# MD1800_5V800mA.net
KiCad netlist of a schematic drawn in Altium Designer
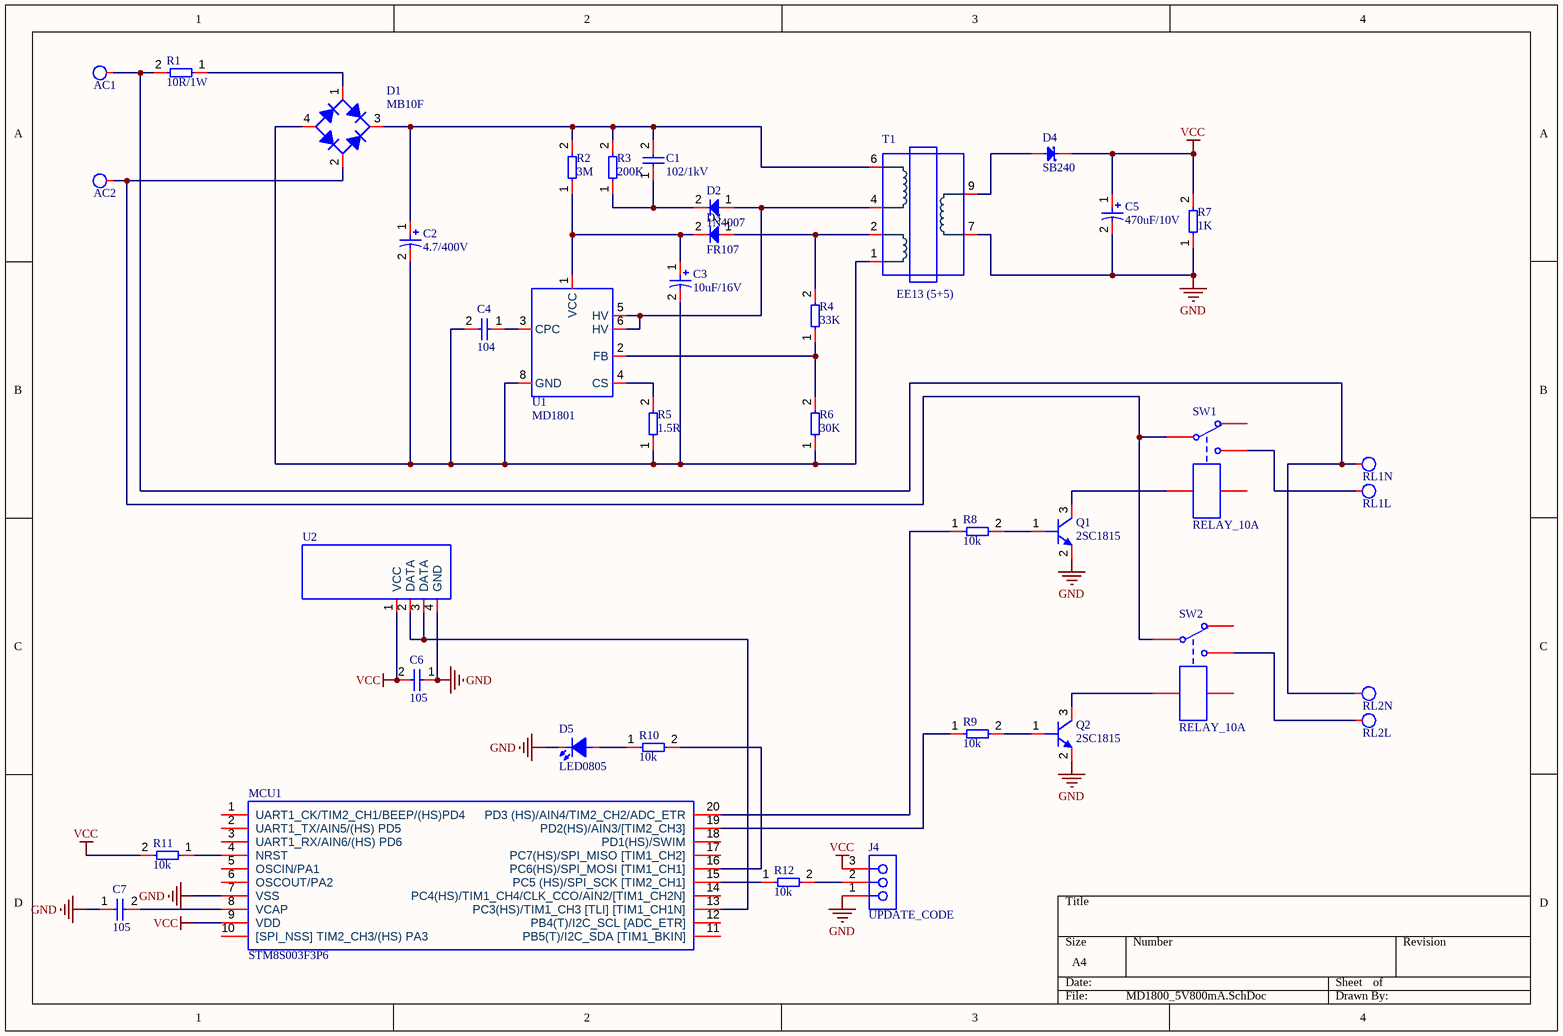
[diagram p0: MD1800_5V800mA.SchDoc]

(export (version "E")
  (design (tool "Eeschema 10.0.6"))
  (components
    (comp (ref "AC1")
      (value "AC")
      (footprint "SolderPoint")
      (libsource (lib "Lib31082020") (part "SolderPoint"))
    )
    (comp (ref "AC2")
      (value "AC")
      (footprint "SolderPoint")
      (libsource (lib "Lib31082020") (part "SolderPoint"))
    )
    (comp (ref "C1") (value "102/1kV") (footprint "C0805") (libsource (lib "Lib31082020") (part "C0805")))
    (comp (ref "C2")
      (value "4.7/400V")
      (footprint "CAP_RAD_3.5mm")
      (libsource (lib "Lib31082020") (part "Capacitor(Radian)"))
    )
    (comp (ref "C3")
      (value "10uF/16V")
      (footprint "CAP_RAD_2.5mm")
      (libsource (lib "Lib31082020") (part "Capacitor(Radian)"))
    )
    (comp (ref "C4") (value "104") (footprint "C0805") (libsource (lib "Lib31082020") (part "C0805")))
    (comp (ref "C5")
      (value "470uF/10V")
      (footprint "CAP_RAD_3.5mm")
      (libsource (lib "Lib31082020") (part "Capacitor(Radian)"))
    )
    (comp (ref "C6") (value "105") (footprint "C0805") (libsource (lib "Lib31082020") (part "C0805")))
    (comp (ref "C7") (value "105") (footprint "C0805") (libsource (lib "Lib31082020") (part "C0805")))
    (comp (ref "D1")
      (value "MB10F")
      (footprint "MB10F-TMBS")
      (description "1A 1000V")
      (libsource (lib "Lib31082020") (part "MB10F"))
    )
    (comp (ref "D2")
      (value "1N4007")
      (footprint "SOD-123FL")
      (description "1A 1000V")
      (libsource (lib "Lib31082020") (part "Diode FR107"))
    )
    (comp (ref "D3")
      (value "FR107")
      (footprint "SOD-123FL")
      (description "1A 1000V")
      (libsource (lib "Lib31082020") (part "Diode FR107"))
    )
    (comp (ref "D4")
      (value "SB240")
      (footprint "DO-214AC(SMA)")
      (libsource (lib "Lib31082020") (part "Diode Schottky"))
    )
    (comp (ref "D5")
      (value "LED0805")
      (footprint "L0805RED")
      (libsource (lib "Lib31082020") (part "LED0805"))
    )
    (comp (ref "J4")
      (value "UPDATE_CODE")
      (footprint "Header 3x1 TH Pitch 2.54mm")
      (libsource (lib "Lib31082020") (part "Header 3x1 TH Pitch 2.54mm"))
    )
    (comp (ref "MCU1")
      (value "STM8S003F3P6")
      (footprint "TSSOP20_0.65_4.4")
      (libsource (lib "Lib31082020") (part "STM8S003F3P6"))
    )
    (comp (ref "Q1")
      (value "2SC1815")
      (footprint "SOT23-3")
      (libsource (lib "Lib31082020") (part "2SC1815 (SOT-23)"))
    )
    (comp (ref "Q2")
      (value "2SC1815")
      (footprint "SOT23-3")
      (libsource (lib "Lib31082020") (part "2SC1815 (SOT-23)"))
    )
    (comp (ref "R1")
      (value "10R/1W")
      (footprint "RES-1W-V-MF")
      (libsource (lib "Lib31082020") (part "Resistors THD"))
    )
    (comp (ref "R2") (value "3M") (footprint "R0805") (libsource (lib "") (part "Resistor SMD_1")))
    (comp (ref "R3") (value "200K") (footprint "R0805") (libsource (lib "") (part "Resistor SMD_1")))
    (comp (ref "R4") (value "33K") (footprint "R0805") (libsource (lib "") (part "Resistor SMD_1")))
    (comp (ref "R5") (value "1.5R") (footprint "R0805") (libsource (lib "") (part "Resistor SMD_1")))
    (comp (ref "R6") (value "30K") (footprint "R0805") (libsource (lib "") (part "Resistor SMD_1")))
    (comp (ref "R7") (value "1K") (footprint "R0805") (libsource (lib "") (part "Resistor SMD_1")))
    (comp (ref "R8") (value "10k") (footprint "R0805") (libsource (lib "Lib31082020") (part "Resistor SMD")))
    (comp (ref "R9") (value "10k") (footprint "R0805") (libsource (lib "Lib31082020") (part "Resistor SMD")))
    (comp (ref "R10") (value "10k") (footprint "R0805") (libsource (lib "Lib31082020") (part "Resistor SMD")))
    (comp (ref "R11") (value "10k") (footprint "R0805") (libsource (lib "") (part "Resistor SMD_2")))
    (comp (ref "R12") (value "10k") (footprint "R0805") (libsource (lib "Lib31082020") (part "Resistor SMD")))
    (comp (ref "RL1L")
      (value "AC")
      (footprint "SolderPoint")
      (libsource (lib "Lib31082020") (part "SolderPoint"))
    )
    (comp (ref "RL1N")
      (value "AC")
      (footprint "SolderPoint")
      (libsource (lib "Lib31082020") (part "SolderPoint"))
    )
    (comp (ref "RL2L")
      (value "AC")
      (footprint "SolderPoint")
      (libsource (lib "Lib31082020") (part "SolderPoint"))
    )
    (comp (ref "RL2N")
      (value "AC")
      (footprint "SolderPoint")
      (libsource (lib "Lib31082020") (part "SolderPoint"))
    )
    (comp (ref "SW1")
      (value "RELAY_10A")
      (footprint "RELAY_10A_5PIN")
      (libsource (lib "Lib31082020") (part "RELAY_10A"))
    )
    (comp (ref "SW2")
      (value "RELAY_10A")
      (footprint "RELAY_10A_5PIN")
      (libsource (lib "Lib31082020") (part "RELAY_10A"))
    )
    (comp (ref "T1")
      (value "EE13 (5+5)")
      (footprint "TRANS_EE19F")
      (libsource (lib "Lib31082020") (part "Trans-EE19F"))
    )
    (comp (ref "U1")
      (value "MD1801")
      (footprint "SOIC-7")
      (description "Power Switching IC")
      (libsource (lib "Lib31082020") (part "MD1801"))
    )
    (comp (ref "U2")
      (value "RF433_315_RECEVICE")
      (footprint "RF433_315_RECEVICE")
      (libsource (lib "Lib31082020") (part "RF433_315"))
    )
  )
  (nets
    (net (code "1") (name "GND") (class "Default")
      (node (ref "C5") (pin "2") (pinfunction "2_2") (pintype "passive"))
      (node (ref "C6") (pin "1") (pinfunction "1_1") (pintype "passive"))
      (node (ref "C7") (pin "1") (pinfunction "1_1") (pintype "passive"))
      (node (ref "D5") (pin "2") (pinfunction "K_2") (pintype "passive"))
      (node (ref "J4") (pin "1") (pinfunction "1_1") (pintype "passive"))
      (node (ref "MCU1") (pin "7") (pinfunction "VSS_7") (pintype "passive"))
      (node (ref "Q1") (pin "2") (pinfunction "E_2") (pintype "passive"))
      (node (ref "Q2") (pin "2") (pinfunction "E_2") (pintype "passive"))
      (node (ref "R7") (pin "1") (pinfunction "1_1") (pintype "passive"))
      (node (ref "T1") (pin "7") (pinfunction "7_7") (pintype "passive"))
      (node (ref "U2") (pin "4") (pinfunction "GND_4") (pintype "passive"))
    )
    (net (code "2") (name "Net-(AC1-Pad1)") (class "Default")
      (node (ref "AC1") (pin "1") (pinfunction "1_1") (pintype "passive"))
      (node (ref "R1") (pin "2") (pinfunction "2_2") (pintype "passive"))
      (node (ref "RL1N") (pin "1") (pinfunction "1_1") (pintype "passive"))
      (node (ref "RL2N") (pin "1") (pinfunction "1_1") (pintype "passive"))
    )
    (net (code "3") (name "Net-(AC2-Pad1)") (class "Default")
      (node (ref "AC2") (pin "1") (pinfunction "1_1") (pintype "passive"))
      (node (ref "D1") (pin "2") (pinfunction "AC_2") (pintype "passive"))
      (node (ref "SW1") (pin "2") (pinfunction "2_2") (pintype "passive"))
      (node (ref "SW2") (pin "2") (pinfunction "2_2") (pintype "passive"))
    )
    (net (code "4") (name "Net-(C1-Pad1)") (class "Default")
      (node (ref "C1") (pin "1") (pinfunction "1_1") (pintype "passive"))
      (node (ref "D2") (pin "2") (pinfunction "2_2") (pintype "passive"))
      (node (ref "R3") (pin "1") (pinfunction "1_1") (pintype "passive"))
    )
    (net (code "5") (name "Net-(D1-+)") (class "Default")
      (node (ref "C1") (pin "2") (pinfunction "2_2") (pintype "passive"))
      (node (ref "C2") (pin "1") (pinfunction "1_1") (pintype "passive"))
      (node (ref "D1") (pin "3") (pinfunction "+_3") (pintype "passive"))
      (node (ref "R2") (pin "2") (pinfunction "2_2") (pintype "passive"))
      (node (ref "R3") (pin "2") (pinfunction "2_2") (pintype "passive"))
      (node (ref "T1") (pin "6") (pinfunction "61_6") (pintype "passive"))
    )
    (net (code "6") (name "Net-(D1--)") (class "Default")
      (node (ref "C2") (pin "2") (pinfunction "2_2") (pintype "passive"))
      (node (ref "C3") (pin "2") (pinfunction "2_2") (pintype "passive"))
      (node (ref "C4") (pin "2") (pinfunction "2_2") (pintype "passive"))
      (node (ref "D1") (pin "4") (pinfunction "-_4") (pintype "passive"))
      (node (ref "R5") (pin "1") (pinfunction "1_1") (pintype "passive"))
      (node (ref "R6") (pin "1") (pinfunction "1_1") (pintype "passive"))
      (node (ref "T1") (pin "1") (pinfunction "1_1") (pintype "passive"))
      (node (ref "U1") (pin "8") (pinfunction "GND_8") (pintype "passive"))
    )
    (net (code "7") (name "Net-(D1-AC-Pad1)") (class "Default")
      (node (ref "D1") (pin "1") (pinfunction "AC_1") (pintype "passive"))
      (node (ref "R1") (pin "1") (pinfunction "1_1") (pintype "passive"))
    )
    (net (code "8") (name "Net-(D2-Pad1)") (class "Default")
      (node (ref "D2") (pin "1") (pinfunction "1_1") (pintype "passive"))
      (node (ref "T1") (pin "4") (pinfunction "4_4") (pintype "passive"))
      (node (ref "U1") (pin "5") (pinfunction "HV_5") (pintype "passive"))
      (node (ref "U1") (pin "6") (pinfunction "HV_6") (pintype "passive"))
    )
    (net (code "9") (name "Net-(D3-Pad1)") (class "Default")
      (node (ref "D3") (pin "1") (pinfunction "1_1") (pintype "passive"))
      (node (ref "R4") (pin "2") (pinfunction "2_2") (pintype "passive"))
      (node (ref "T1") (pin "2") (pinfunction "2_2") (pintype "passive"))
    )
    (net (code "10") (name "Net-(D4-A)") (class "Default")
      (node (ref "D4") (pin "1") (pinfunction "A_1") (pintype "passive"))
      (node (ref "T1") (pin "9") (pinfunction "9_9") (pintype "passive"))
    )
    (net (code "11") (name "Net-(D5-A)") (class "Default")
      (node (ref "D5") (pin "1") (pinfunction "A_1") (pintype "passive"))
      (node (ref "R10") (pin "1") (pinfunction "1_1") (pintype "passive"))
    )
    (net (code "12") (name "Net-(J4-Pad2)") (class "Default")
      (node (ref "J4") (pin "2") (pinfunction "2_2") (pintype "passive"))
      (node (ref "R12") (pin "2") (pinfunction "2_2") (pintype "passive"))
    )
    (net (code "13") (name "Net-(MCU1-NRST)") (class "Default")
      (node (ref "MCU1") (pin "4") (pinfunction "NRST_4") (pintype "passive"))
      (node (ref "R11") (pin "1") (pinfunction "1_1") (pintype "passive"))
    )
    (net (code "14") (name "Net-(MCU1-PC3(HS){slash}TIM1_CH3_[TLI]_[TIM1_CH1N])") (class "Default")
      (node (ref "MCU1") (pin "13") (pinfunction "PC3(HS)/TIM1_CH3_[TLI]_[TIM1_CH1N]_13") (pintype "passive"))
      (node (ref "U2") (pin "2") (pinfunction "DATA_2") (pintype "passive"))
      (node (ref "U2") (pin "3") (pinfunction "DATA_3") (pintype "passive"))
    )
    (net (code "15") (name "Net-(MCU1-PC5_(HS){slash}SPI_SCK_[TIM2_CH1])") (class "Default")
      (node (ref "MCU1") (pin "15") (pinfunction "PC5_(HS)/SPI_SCK_[TIM2_CH1]_15") (pintype "passive"))
      (node (ref "R12") (pin "1") (pinfunction "1_1") (pintype "passive"))
    )
    (net (code "16") (name "Net-(MCU1-PC6(HS){slash}SPI_MOSI_[TIM1_CH1])") (class "Default")
      (node (ref "MCU1") (pin "16") (pinfunction "PC6(HS)/SPI_MOSI_[TIM1_CH1]_16") (pintype "passive"))
      (node (ref "R10") (pin "2") (pinfunction "2_2") (pintype "passive"))
    )
    (net (code "17") (name "Net-(MCU1-PD2(HS){slash}AIN3{slash}[TIM2_CH3])") (class "Default")
      (node (ref "MCU1") (pin "19") (pinfunction "PD2(HS)/AIN3/[TIM2_CH3]_19") (pintype "passive"))
      (node (ref "R9") (pin "1") (pinfunction "1_1") (pintype "passive"))
    )
    (net (code "18") (name "Net-(MCU1-PD3_(HS){slash}AIN4{slash}TIM2_CH2{slash}ADC_ETR)") (class "Default")
      (node (ref "MCU1") (pin "20") (pinfunction "PD3_(HS)/AIN4/TIM2_CH2/ADC_ETR_20") (pintype "passive"))
      (node (ref "R8") (pin "1") (pinfunction "1_1") (pintype "passive"))
    )
    (net (code "19") (name "Net-(MCU1-VCAP)") (class "Default")
      (node (ref "C7") (pin "2") (pinfunction "2_2") (pintype "passive"))
      (node (ref "MCU1") (pin "8") (pinfunction "VCAP_8") (pintype "passive"))
    )
    (net (code "20") (name "Net-(Q1-B)") (class "Default")
      (node (ref "Q1") (pin "1") (pinfunction "B_1") (pintype "passive"))
      (node (ref "R8") (pin "2") (pinfunction "2_2") (pintype "passive"))
    )
    (net (code "21") (name "Net-(Q1-C)") (class "Default")
      (node (ref "Q1") (pin "3") (pinfunction "C_3") (pintype "passive"))
      (node (ref "SW1") (pin "1") (pinfunction "1_1") (pintype "passive"))
    )
    (net (code "22") (name "Net-(Q2-B)") (class "Default")
      (node (ref "Q2") (pin "1") (pinfunction "B_1") (pintype "passive"))
      (node (ref "R9") (pin "2") (pinfunction "2_2") (pintype "passive"))
    )
    (net (code "23") (name "Net-(Q2-C)") (class "Default")
      (node (ref "Q2") (pin "3") (pinfunction "C_3") (pintype "passive"))
      (node (ref "SW2") (pin "1") (pinfunction "1_1") (pintype "passive"))
    )
    (net (code "24") (name "Net-(RL1L-Pad1)") (class "Default")
      (node (ref "RL1L") (pin "1") (pinfunction "1_1") (pintype "passive"))
      (node (ref "SW1") (pin "5") (pinfunction "5_5") (pintype "passive"))
    )
    (net (code "25") (name "Net-(RL2L-Pad1)") (class "Default")
      (node (ref "RL2L") (pin "1") (pinfunction "1_1") (pintype "passive"))
      (node (ref "SW2") (pin "5") (pinfunction "5_5") (pintype "passive"))
    )
    (net (code "26") (name "Net-(U1-CPC)") (class "Default")
      (node (ref "C4") (pin "1") (pinfunction "1_1") (pintype "passive"))
      (node (ref "U1") (pin "3") (pinfunction "CPC_3") (pintype "passive"))
    )
    (net (code "27") (name "Net-(U1-CS)") (class "Default")
      (node (ref "R5") (pin "2") (pinfunction "2_2") (pintype "passive"))
      (node (ref "U1") (pin "4") (pinfunction "CS_4") (pintype "passive"))
    )
    (net (code "28") (name "Net-(U1-FB)") (class "Default")
      (node (ref "R4") (pin "1") (pinfunction "1_1") (pintype "passive"))
      (node (ref "R6") (pin "2") (pinfunction "2_2") (pintype "passive"))
      (node (ref "U1") (pin "2") (pinfunction "FB_2") (pintype "passive"))
    )
    (net (code "29") (name "Net-(U1-VCC)") (class "Default")
      (node (ref "C3") (pin "1") (pinfunction "1_1") (pintype "passive"))
      (node (ref "D3") (pin "2") (pinfunction "2_2") (pintype "passive"))
      (node (ref "R2") (pin "1") (pinfunction "1_1") (pintype "passive"))
      (node (ref "U1") (pin "1") (pinfunction "VCC_1") (pintype "passive"))
    )
    (net (code "30") (name "VCC") (class "Default")
      (node (ref "C5") (pin "1") (pinfunction "1_1") (pintype "passive"))
      (node (ref "C6") (pin "2") (pinfunction "2_2") (pintype "passive"))
      (node (ref "D4") (pin "2") (pinfunction "K_2") (pintype "passive"))
      (node (ref "J4") (pin "3") (pinfunction "3_3") (pintype "passive"))
      (node (ref "MCU1") (pin "9") (pinfunction "VDD_9") (pintype "passive"))
      (node (ref "R11") (pin "2") (pinfunction "2_2") (pintype "passive"))
      (node (ref "R7") (pin "2") (pinfunction "2_2") (pintype "passive"))
      (node (ref "U2") (pin "1") (pinfunction "VCC_1") (pintype "passive"))
    )
    (net (code "31") (name "unconnected-(MCU1-OSCIN{slash}PA1-Pad5)") (class "Default")
      (node (ref "MCU1") (pin "5") (pinfunction "OSCIN/PA1_5") (pintype "passive"))
    )
    (net (code "32") (name "unconnected-(MCU1-OSCOUT{slash}PA2-Pad6)") (class "Default")
      (node (ref "MCU1") (pin "6") (pinfunction "OSCOUT/PA2_6") (pintype "passive"))
    )
    (net (code "33") (name "unconnected-(MCU1-PB4(T){slash}I2C_SCL_[ADC_ETR]-Pad12)") (class "Default")
      (node (ref "MCU1") (pin "12") (pinfunction "PB4(T)/I2C_SCL_[ADC_ETR]_12") (pintype "passive"))
    )
    (net (code "34") (name "unconnected-(MCU1-PB5(T){slash}I2C_SDA_[TIM1_BKIN]-Pad11)") (class "Default")
      (node (ref "MCU1") (pin "11") (pinfunction "PB5(T)/I2C_SDA_[TIM1_BKIN]_11") (pintype "passive"))
    )
    (net (code "35") (name "unconnected-(MCU1-PC4(HS){slash}TIM1_CH4{slash}CLK_CCO{slash}AIN2{slash}[TIM1_CH2N]-Pad14)") (class "Default")
      (node (ref "MCU1") (pin "14") (pinfunction "PC4(HS)/TIM1_CH4/CLK_CCO/AIN2/[TIM1_CH2N]_14") (pintype "passive"))
    )
    (net (code "36") (name "unconnected-(MCU1-PC7(HS){slash}SPI_MISO_[TIM1_CH2]-Pad17)") (class "Default")
      (node (ref "MCU1") (pin "17") (pinfunction "PC7(HS)/SPI_MISO_[TIM1_CH2]_17") (pintype "passive"))
    )
    (net (code "37") (name "unconnected-(MCU1-PD1(HS){slash}SWIM-Pad18)") (class "Default")
      (node (ref "MCU1") (pin "18") (pinfunction "PD1(HS)/SWIM_18") (pintype "passive"))
    )
    (net (code "38") (name "unconnected-(MCU1-UART1_CK{slash}TIM2_CH1{slash}BEEP{slash}(HS)PD4-Pad1)") (class "Default")
      (node (ref "MCU1") (pin "1") (pinfunction "UART1_CK/TIM2_CH1/BEEP/(HS)PD4_1") (pintype "passive"))
    )
    (net (code "39") (name "unconnected-(MCU1-UART1_RX{slash}AIN6{slash}(HS)_PD6-Pad3)") (class "Default")
      (node (ref "MCU1") (pin "3") (pinfunction "UART1_RX/AIN6/(HS)_PD6_3") (pintype "passive"))
    )
    (net (code "40") (name "unconnected-(MCU1-UART1_TX{slash}AIN5{slash}(HS)_PD5-Pad2)") (class "Default")
      (node (ref "MCU1") (pin "2") (pinfunction "UART1_TX/AIN5/(HS)_PD5_2") (pintype "passive"))
    )
    (net (code "41") (name "unconnected-(MCU1-[SPI_NSS]_TIM2_CH3{slash}(HS)_PA3-Pad10)") (class "Default")
      (node (ref "MCU1") (pin "10") (pinfunction "[SPI_NSS]_TIM2_CH3/(HS)_PA3_10") (pintype "passive"))
    )
    (net (code "42") (name "unconnected-(SW1-Pad3)") (class "Default")
      (node (ref "SW1") (pin "3") (pinfunction "3_3") (pintype "passive"))
    )
    (net (code "43") (name "unconnected-(SW1-Pad4)") (class "Default")
      (node (ref "SW1") (pin "4") (pinfunction "4_4") (pintype "passive"))
    )
    (net (code "44") (name "unconnected-(SW2-Pad3)") (class "Default")
      (node (ref "SW2") (pin "3") (pinfunction "3_3") (pintype "passive"))
    )
    (net (code "45") (name "unconnected-(SW2-Pad4)") (class "Default")
      (node (ref "SW2") (pin "4") (pinfunction "4_4") (pintype "passive"))
    )
  )
)
